# filtro2.net
KiCad netlist of a schematic drawn in Altium Designer
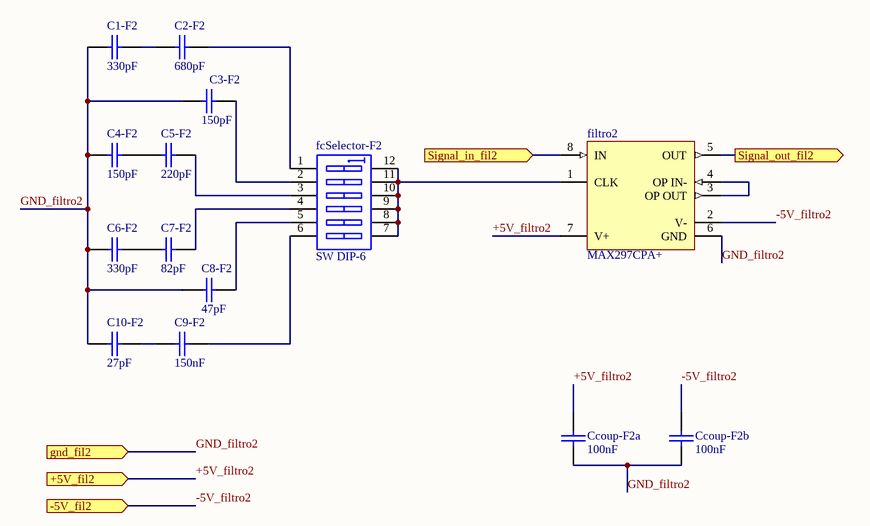
[diagram p0: filtro2.SchDoc]

(export (version "E")
  (design (tool "Eeschema 10.0.6"))
  (components
    (comp (ref "C1-F2") (value "330pF") (footprint "CAP200") (libsource (lib "LIBEBAL") (part "CAP")))
    (comp (ref "C2-F2") (value "680pF") (footprint "CAP200") (libsource (lib "LIBEBAL") (part "CAP")))
    (comp (ref "C3-F2") (value "150pF") (footprint "CAP200") (libsource (lib "LIBEBAL") (part "CAP")))
    (comp (ref "C4-F2") (value "150pF") (footprint "CAP200") (libsource (lib "LIBEBAL") (part "CAP")))
    (comp (ref "C5-F2") (value "220pF") (footprint "CAP200") (libsource (lib "LIBEBAL") (part "CAP")))
    (comp (ref "C6-F2") (value "330pF") (footprint "CAP200") (libsource (lib "LIBEBAL") (part "CAP")))
    (comp (ref "C7-F2") (value "82pF") (footprint "CAP200") (libsource (lib "LIBEBAL") (part "CAP")))
    (comp (ref "C8-F2") (value "47pF") (footprint "CAP200") (libsource (lib "LIBEBAL") (part "CAP")))
    (comp (ref "C9-F2") (value "150nF") (footprint "CAP200") (libsource (lib "LIBEBAL") (part "CAP")))
    (comp (ref "C10-F2") (value "27pF") (footprint "CAP200") (libsource (lib "LIBEBAL") (part "CAP")))
    (comp (ref "Ccoup-F2a") (value "100nF") (footprint "CAP200") (libsource (lib "LIBEBAL") (part "CAP")))
    (comp (ref "Ccoup-F2b") (value "100nF") (footprint "CAP200") (libsource (lib "LIBEBAL") (part "CAP")))
    (comp (ref "fcSelector-F2")
      (value "SW DIP-6")
      (footprint "DIP-12/SW")
      (description "DIP Switch, 6 Position, SPST")
      (fields (field (name "PUBLISHER") "Altium Limited"))
      (libsource (lib "Miscellaneous Devices") (part "SW DIP-6"))
    )
    (comp (ref "filtro2")
      (value "MAX297CPA+")
      (footprint "MAXM-P8+2")
      (fields (field (name "GENERIC PART NUMBER") "MAX297"))
      (libsource (lib "Maxim Analog Filters") (part "MAX297CPA+"))
    )
  )
  (nets
    (net (code "1") (name "/+5V_filtro2") (class "Default")
      (node (ref "Ccoup-F2a") (pin "2") (pinfunction "2_2") (pintype "passive"))
      (node (ref "filtro2") (pin "7") (pinfunction "V+_7") (pintype "power_in"))
    )
    (net (code "2") (name "/-5V_filtro2") (class "Default")
      (node (ref "Ccoup-F2b") (pin "2") (pinfunction "2_2") (pintype "passive"))
      (node (ref "filtro2") (pin "2") (pinfunction "V-_2") (pintype "power_in"))
    )
    (net (code "3") (name "/GND_filtro2") (class "Default")
      (node (ref "C1-F2") (pin "1") (pinfunction "1_1") (pintype "passive"))
      (node (ref "C10-F2") (pin "1") (pinfunction "1_1") (pintype "passive"))
      (node (ref "C3-F2") (pin "1") (pinfunction "1_1") (pintype "passive"))
      (node (ref "C4-F2") (pin "1") (pinfunction "1_1") (pintype "passive"))
      (node (ref "C6-F2") (pin "1") (pinfunction "1_1") (pintype "passive"))
      (node (ref "C8-F2") (pin "1") (pinfunction "1_1") (pintype "passive"))
      (node (ref "Ccoup-F2a") (pin "1") (pinfunction "1_1") (pintype "passive"))
      (node (ref "Ccoup-F2b") (pin "1") (pinfunction "1_1") (pintype "passive"))
      (node (ref "filtro2") (pin "6") (pinfunction "GND_6") (pintype "power_in"))
    )
    (net (code "4") (name "/Signal_in_fil2") (class "Default")
      (node (ref "filtro2") (pin "8") (pinfunction "IN_8") (pintype "input"))
    )
    (net (code "5") (name "/Signal_out_fil2") (class "Default")
      (node (ref "filtro2") (pin "5") (pinfunction "OUT_5") (pintype "output"))
    )
    (net (code "6") (name "Net-(C1-F2-Pad2)") (class "Default")
      (node (ref "C1-F2") (pin "2") (pinfunction "2_2") (pintype "passive"))
      (node (ref "C2-F2") (pin "1") (pinfunction "1_1") (pintype "passive"))
    )
    (net (code "7") (name "Net-(C4-F2-Pad2)") (class "Default")
      (node (ref "C4-F2") (pin "2") (pinfunction "2_2") (pintype "passive"))
      (node (ref "C5-F2") (pin "1") (pinfunction "1_1") (pintype "passive"))
    )
    (net (code "8") (name "Net-(C6-F2-Pad2)") (class "Default")
      (node (ref "C6-F2") (pin "2") (pinfunction "2_2") (pintype "passive"))
      (node (ref "C7-F2") (pin "1") (pinfunction "1_1") (pintype "passive"))
    )
    (net (code "9") (name "Net-(C10-F2-Pad2)") (class "Default")
      (node (ref "C10-F2") (pin "2") (pinfunction "2_2") (pintype "passive"))
      (node (ref "C9-F2") (pin "1") (pinfunction "1_1") (pintype "passive"))
    )
    (net (code "10") (name "Net-(fcSelector-F2-A1)") (class "Default")
      (node (ref "C2-F2") (pin "2") (pinfunction "2_2") (pintype "passive"))
      (node (ref "fcSelector-F2") (pin "1") (pinfunction "A1_1") (pintype "passive"))
    )
    (net (code "11") (name "Net-(fcSelector-F2-A2)") (class "Default")
      (node (ref "C3-F2") (pin "2") (pinfunction "2_2") (pintype "passive"))
      (node (ref "fcSelector-F2") (pin "2") (pinfunction "A2_2") (pintype "passive"))
    )
    (net (code "12") (name "Net-(fcSelector-F2-A3)") (class "Default")
      (node (ref "C5-F2") (pin "2") (pinfunction "2_2") (pintype "passive"))
      (node (ref "fcSelector-F2") (pin "3") (pinfunction "A3_3") (pintype "passive"))
    )
    (net (code "13") (name "Net-(fcSelector-F2-A4)") (class "Default")
      (node (ref "C7-F2") (pin "2") (pinfunction "2_2") (pintype "passive"))
      (node (ref "fcSelector-F2") (pin "4") (pinfunction "A4_4") (pintype "passive"))
    )
    (net (code "14") (name "Net-(fcSelector-F2-A5)") (class "Default")
      (node (ref "C8-F2") (pin "2") (pinfunction "2_2") (pintype "passive"))
      (node (ref "fcSelector-F2") (pin "5") (pinfunction "A5_5") (pintype "passive"))
    )
    (net (code "15") (name "Net-(fcSelector-F2-A6)") (class "Default")
      (node (ref "C9-F2") (pin "2") (pinfunction "2_2") (pintype "passive"))
      (node (ref "fcSelector-F2") (pin "6") (pinfunction "A6_6") (pintype "passive"))
    )
    (net (code "16") (name "Net-(fcSelector-F2-B1)") (class "Default")
      (node (ref "fcSelector-F2") (pin "10") (pinfunction "B3_10") (pintype "passive"))
      (node (ref "fcSelector-F2") (pin "11") (pinfunction "B2_11") (pintype "passive"))
      (node (ref "fcSelector-F2") (pin "12") (pinfunction "B1_12") (pintype "passive"))
      (node (ref "fcSelector-F2") (pin "7") (pinfunction "B6_7") (pintype "passive"))
      (node (ref "fcSelector-F2") (pin "8") (pinfunction "B5_8") (pintype "passive"))
      (node (ref "fcSelector-F2") (pin "9") (pinfunction "B4_9") (pintype "passive"))
      (node (ref "filtro2") (pin "1") (pinfunction "CLK_1") (pintype "passive"))
    )
    (net (code "17") (name "Net-(filtro2-OP_IN-)") (class "Default")
      (node (ref "filtro2") (pin "3") (pinfunction "OP_OUT_3") (pintype "output"))
      (node (ref "filtro2") (pin "4") (pinfunction "OP_IN-_4") (pintype "input"))
    )
  )
)
